# temp_sense.net
KiCad netlist of a schematic drawn in Altium Designer
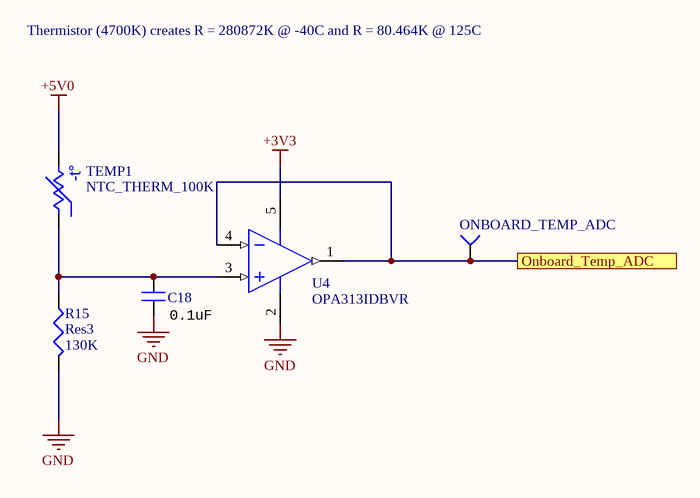
[diagram p0: temp_sense.SchDoc]

(export (version "E")
  (design (tool "Eeschema 10.0.6"))
  (components
    (comp (ref "C18")
      (value "0.1uF")
      (footprint "CAPC0603(1608)55_N")
      (description "CAP CER 0.1UF 16V X7R 0603")
      (fields (field (name "MPN") "CC0603KRX7R7BB104") (field (name "MANUFACTURER") "Yageo"))
      (libsource (lib "*") (part "CAP_0.1uF_16V_0603"))
    )
    (comp (ref "ONBOARD_TEMP_ADC")
      (value "ONBOARD_TEMP_ADC")
      (footprint "TESTPOINT")
      (description "TESTPOINT_SMD")
      (libsource (lib "UWRT_Schematic_Library_2020") (part "TESTPOINT_SMD"))
    )
    (comp (ref "R15")
      (value "Res3")
      (footprint "J1-0603")
      (description "Resistor")
      (fields (field (name "ALTIUM_VALUE") "130K") (field (name "PUBLISHER") "Altium Limited"))
      (libsource (lib "Miscellaneous Devices") (part "Res3"))
    )
    (comp (ref "TEMP1")
      (value "NTC_THERM_100K")
      (footprint "RESC0603(1608)_N")
      (description "THERM NTC 100KOHM 4700K 0603")
      (fields (field (name "MPN") "ERT-J1VV104J") (field (name "DIGIKEY PART NUMBER") "P10555CT-ND"))
      (libsource (lib "UWRT_Schematic_Library_2020") (part "NTC_THERM_100K"))
    )
    (comp (ref "U4")
      (value "OPA313IDBVR")
      (footprint "DBV0005A_M")
      (fields
        (field (name "MANUFACTURER") "Texas Instruments")
        (field (name "DIGI-KEY PART NUMBER") "296-35607-1-ND")
      )
      (libsource (lib "UWRT_Schematic_Library_2020") (part "OPAMP"))
    )
  )
  (nets
    (net (code "1") (name "+3V3") (class "Default")
      (node (ref "U4") (pin "5") (pinfunction "V+_5") (pintype "power_in"))
    )
    (net (code "2") (name "+5V0") (class "Default")
      (node (ref "TEMP1") (pin "1") (pinfunction "1_1") (pintype "passive"))
    )
    (net (code "3") (name "/Onboard_Temp_ADC") (class "Default")
      (node (ref "ONBOARD_TEMP_ADC") (pin "1") (pinfunction "=value_1") (pintype "passive"))
      (node (ref "U4") (pin "1") (pinfunction "OUT_1") (pintype "output"))
      (node (ref "U4") (pin "4") (pinfunction "IN-_4") (pintype "input"))
    )
    (net (code "4") (name "GND") (class "Default")
      (node (ref "C18") (pin "1") (pinfunction "1_1") (pintype "passive"))
      (node (ref "R15") (pin "2") (pinfunction "2_2") (pintype "passive"))
      (node (ref "U4") (pin "2") (pinfunction "V-_2") (pintype "power_in"))
    )
    (net (code "5") (name "Net-(U4-IN+)") (class "Default")
      (node (ref "C18") (pin "2") (pinfunction "2_2") (pintype "passive"))
      (node (ref "R15") (pin "1") (pinfunction "1_1") (pintype "passive"))
      (node (ref "TEMP1") (pin "2") (pinfunction "2_2") (pintype "passive"))
      (node (ref "U4") (pin "3") (pinfunction "IN+_3") (pintype "input"))
    )
  )
)
